# draft1.net
KiCad netlist of a schematic drawn in EAGLE
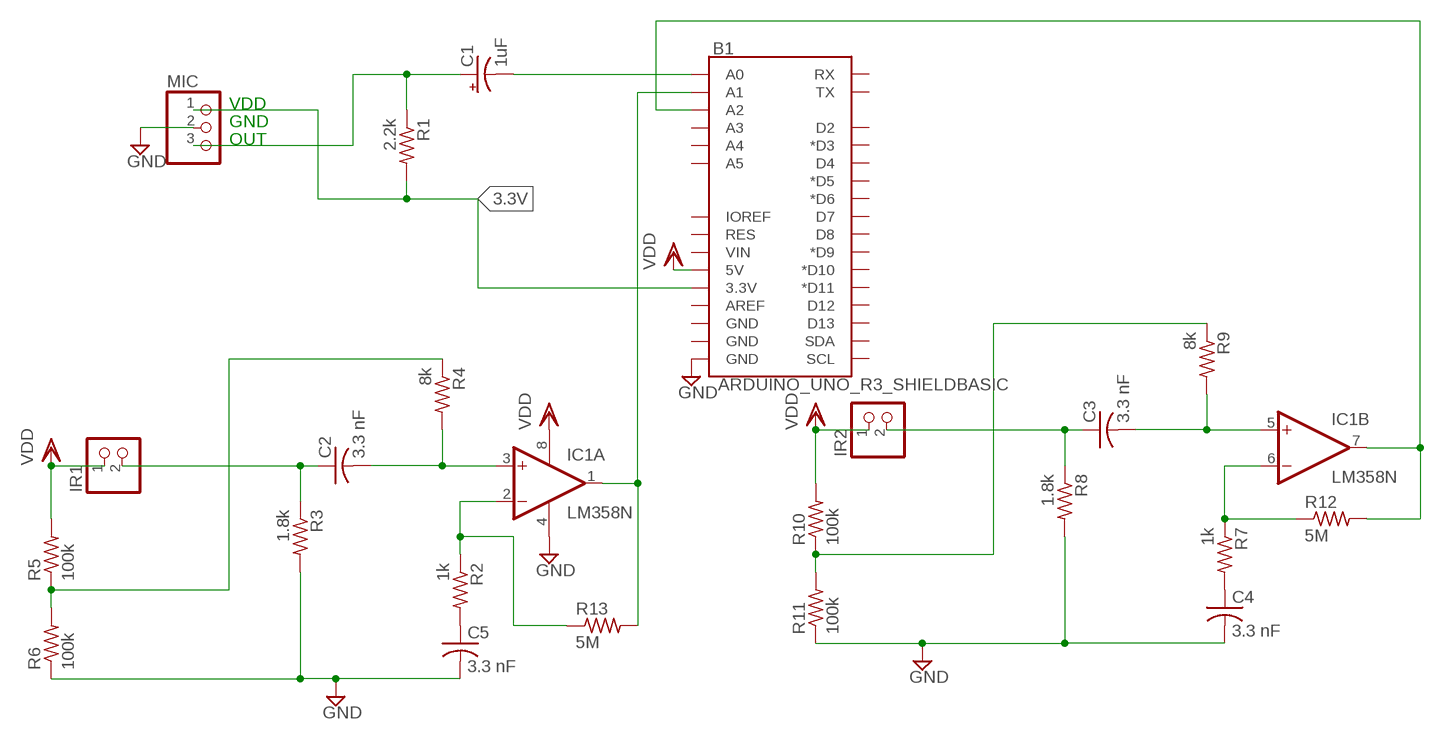
[diagram p0: schematic, sheet 1]

(export (version "E")
  (design (tool "Eeschema 10.0.6"))
  (components
    (comp (ref "B1")
      (value "ARDUINO_UNO_R3_SHIELDBASIC")
      (footprint "eagle-import:UNO_R3_SHIELD")
      (libsource (lib "eagle-import") (part "ARDUINO_UNO_R3_SHIELDBASIC"))
    )
    (comp (ref "C1")
      (value "1uF")
      (footprint "eagle-import:E5-6")
      (libsource (lib "eagle-import") (part "CPOL-USE5-6"))
    )
    (comp (ref "C2")
      (value "3.3 nF")
      (footprint "eagle-import:C025-040X050")
      (libsource (lib "eagle-import") (part "C-US025-040X050"))
    )
    (comp (ref "C3")
      (value "3.3 nF")
      (footprint "eagle-import:C025-040X050")
      (libsource (lib "eagle-import") (part "C-US025-040X050"))
    )
    (comp (ref "C4")
      (value "3.3 nF")
      (footprint "eagle-import:C025-040X050")
      (libsource (lib "eagle-import") (part "C-US025-040X050"))
    )
    (comp (ref "C5")
      (value "3.3 nF")
      (footprint "eagle-import:C025-040X050")
      (libsource (lib "eagle-import") (part "C-US025-040X050"))
    )
    (comp (ref "IC1")
      (value "LM358N")
      (footprint "eagle-import:DIL08")
      (libsource (lib "eagle-import") (part "LM358N"))
    )
    (comp (ref "IR1")
      (value "PINHD-1X2")
      (footprint "eagle-import:1X02")
      (libsource (lib "eagle-import") (part "PINHD-1X2"))
    )
    (comp (ref "IR2")
      (value "PINHD-1X2")
      (footprint "eagle-import:1X02")
      (libsource (lib "eagle-import") (part "PINHD-1X2"))
    )
    (comp (ref "MIC")
      (value "PINHD-1X3")
      (footprint "eagle-import:1X03")
      (libsource (lib "eagle-import") (part "PINHD-1X3"))
    )
    (comp (ref "R1")
      (value "2.2k")
      (footprint "eagle-import:0207_7")
      (libsource (lib "eagle-import") (part "rcl_334_R-US_0207/7"))
    )
    (comp (ref "R2")
      (value "1k")
      (footprint "eagle-import:0207_7")
      (libsource (lib "eagle-import") (part "rcl_334_R-US_0207/7"))
    )
    (comp (ref "R3")
      (value "1.8k")
      (footprint "eagle-import:0207_7")
      (libsource (lib "eagle-import") (part "rcl_334_R-US_0207/7"))
    )
    (comp (ref "R4")
      (value "8k")
      (footprint "eagle-import:0207_7")
      (libsource (lib "eagle-import") (part "rcl_334_R-US_0207/7"))
    )
    (comp (ref "R5")
      (value "100k")
      (footprint "eagle-import:0207_7")
      (libsource (lib "eagle-import") (part "R-US_0207/7"))
    )
    (comp (ref "R6")
      (value "100k")
      (footprint "eagle-import:0207_7")
      (libsource (lib "eagle-import") (part "R-US_0207/7"))
    )
    (comp (ref "R7")
      (value "1k")
      (footprint "eagle-import:0207_7")
      (libsource (lib "eagle-import") (part "rcl_334_R-US_0207/7"))
    )
    (comp (ref "R8")
      (value "1.8k")
      (footprint "eagle-import:0207_7")
      (libsource (lib "eagle-import") (part "rcl_334_R-US_0207/7"))
    )
    (comp (ref "R9")
      (value "8k")
      (footprint "eagle-import:0207_7")
      (libsource (lib "eagle-import") (part "rcl_334_R-US_0207/7"))
    )
    (comp (ref "R10")
      (value "100k")
      (footprint "eagle-import:0207_7")
      (libsource (lib "eagle-import") (part "R-US_0207/7"))
    )
    (comp (ref "R11")
      (value "100k")
      (footprint "eagle-import:0207_7")
      (libsource (lib "eagle-import") (part "R-US_0207/7"))
    )
    (comp (ref "R12")
      (value "5M")
      (footprint "eagle-import:0207_7")
      (libsource (lib "eagle-import") (part "rcl_334_R-US_0207/7"))
    )
    (comp (ref "R13")
      (value "5M")
      (footprint "eagle-import:0207_7")
      (libsource (lib "eagle-import") (part "rcl_334_R-US_0207/7"))
    )
  )
  (nets
    (net (code "1") (name "3.3V") (class "Default")
      (node (ref "B1") (pin "3.3V") (pinfunction "3.3V_3.3V") (pintype "bidirectional"))
      (node (ref "MIC") (pin "1") (pinfunction "1_1") (pintype "passive"))
      (node (ref "R1") (pin "2") (pinfunction "2_2") (pintype "passive"))
    )
    (net (code "2") (name "GND") (class "Default")
      (node (ref "B1") (pin "GND@0") (pinfunction "GND_GND@0") (pintype "bidirectional"))
      (node (ref "C4") (pin "2") (pinfunction "2_2") (pintype "passive"))
      (node (ref "C5") (pin "2") (pinfunction "2_2") (pintype "passive"))
      (node (ref "IC1") (pin "4") (pinfunction "V-_4") (pintype "power_in"))
      (node (ref "MIC") (pin "2") (pinfunction "2_2") (pintype "passive"))
      (node (ref "R11") (pin "1") (pinfunction "1_1") (pintype "passive"))
      (node (ref "R3") (pin "2") (pinfunction "2_2") (pintype "passive"))
      (node (ref "R6") (pin "1") (pinfunction "1_1") (pintype "passive"))
      (node (ref "R8") (pin "2") (pinfunction "2_2") (pintype "passive"))
    )
    (net (code "3") (name "Net-(B1-PadA0)") (class "Default")
      (node (ref "B1") (pin "A0") (pinfunction "A0_A0") (pintype "bidirectional"))
      (node (ref "C1") (pin "-") (pinfunction "-_-") (pintype "passive"))
    )
    (net (code "4") (name "Net-(C1-Pad+)") (class "Default")
      (node (ref "C1") (pin "+") (pinfunction "+_+") (pintype "passive"))
      (node (ref "MIC") (pin "3") (pinfunction "3_3") (pintype "passive"))
      (node (ref "R1") (pin "1") (pinfunction "1_1") (pintype "passive"))
    )
    (net (code "5") (name "Net-(C2-Pad1)") (class "Default")
      (node (ref "C2") (pin "1") (pinfunction "1_1") (pintype "passive"))
      (node (ref "IR1") (pin "2") (pinfunction "2_2") (pintype "passive"))
      (node (ref "R3") (pin "1") (pinfunction "1_1") (pintype "passive"))
    )
    (net (code "6") (name "Net-(C3-Pad1)") (class "Default")
      (node (ref "C3") (pin "1") (pinfunction "1_1") (pintype "passive"))
      (node (ref "IR2") (pin "2") (pinfunction "2_2") (pintype "passive"))
      (node (ref "R8") (pin "1") (pinfunction "1_1") (pintype "passive"))
    )
    (net (code "7") (name "Net-(C4-Pad1)") (class "Default")
      (node (ref "C4") (pin "1") (pinfunction "1_1") (pintype "passive"))
      (node (ref "R7") (pin "2") (pinfunction "2_2") (pintype "passive"))
    )
    (net (code "8") (name "Net-(C5-Pad1)") (class "Default")
      (node (ref "C5") (pin "1") (pinfunction "1_1") (pintype "passive"))
      (node (ref "R2") (pin "2") (pinfunction "2_2") (pintype "passive"))
    )
    (net (code "9") (name "Net-(IC1A-+IN)") (class "Default")
      (node (ref "C2") (pin "2") (pinfunction "2_2") (pintype "passive"))
      (node (ref "IC1") (pin "3") (pinfunction "+IN_3") (pintype "input"))
      (node (ref "R4") (pin "2") (pinfunction "2_2") (pintype "passive"))
    )
    (net (code "10") (name "Net-(IC1A--IN)") (class "Default")
      (node (ref "IC1") (pin "2") (pinfunction "-IN_2") (pintype "input"))
      (node (ref "R13") (pin "1") (pinfunction "1_1") (pintype "passive"))
      (node (ref "R2") (pin "1") (pinfunction "1_1") (pintype "passive"))
    )
    (net (code "11") (name "Net-(IC1A-OUT)") (class "Default")
      (node (ref "B1") (pin "A1") (pinfunction "A1_A1") (pintype "bidirectional"))
      (node (ref "IC1") (pin "1") (pinfunction "OUT_1") (pintype "output"))
      (node (ref "R13") (pin "2") (pinfunction "2_2") (pintype "passive"))
    )
    (net (code "12") (name "Net-(IC1B-+IN)") (class "Default")
      (node (ref "C3") (pin "2") (pinfunction "2_2") (pintype "passive"))
      (node (ref "IC1") (pin "5") (pinfunction "+IN_5") (pintype "input"))
      (node (ref "R9") (pin "2") (pinfunction "2_2") (pintype "passive"))
    )
    (net (code "13") (name "Net-(IC1B--IN)") (class "Default")
      (node (ref "IC1") (pin "6") (pinfunction "-IN_6") (pintype "input"))
      (node (ref "R12") (pin "1") (pinfunction "1_1") (pintype "passive"))
      (node (ref "R7") (pin "1") (pinfunction "1_1") (pintype "passive"))
    )
    (net (code "14") (name "Net-(IC1B-OUT)") (class "Default")
      (node (ref "B1") (pin "A2") (pinfunction "A2_A2") (pintype "bidirectional"))
      (node (ref "IC1") (pin "7") (pinfunction "OUT_7") (pintype "output"))
      (node (ref "R12") (pin "2") (pinfunction "2_2") (pintype "passive"))
    )
    (net (code "15") (name "Net-(R4-Pad1)") (class "Default")
      (node (ref "R4") (pin "1") (pinfunction "1_1") (pintype "passive"))
      (node (ref "R5") (pin "1") (pinfunction "1_1") (pintype "passive"))
      (node (ref "R6") (pin "2") (pinfunction "2_2") (pintype "passive"))
    )
    (net (code "16") (name "Net-(R10-Pad1)") (class "Default")
      (node (ref "R10") (pin "1") (pinfunction "1_1") (pintype "passive"))
      (node (ref "R11") (pin "2") (pinfunction "2_2") (pintype "passive"))
      (node (ref "R9") (pin "1") (pinfunction "1_1") (pintype "passive"))
    )
    (net (code "17") (name "VDD") (class "Default")
      (node (ref "B1") (pin "5V") (pinfunction "5V_5V") (pintype "bidirectional"))
      (node (ref "IC1") (pin "8") (pinfunction "V+_8") (pintype "power_in"))
      (node (ref "IR1") (pin "1") (pinfunction "1_1") (pintype "passive"))
      (node (ref "IR2") (pin "1") (pinfunction "1_1") (pintype "passive"))
      (node (ref "R10") (pin "2") (pinfunction "2_2") (pintype "passive"))
      (node (ref "R5") (pin "2") (pinfunction "2_2") (pintype "passive"))
    )
    (net (code "18") (name "unconnected-(B1-*D3-PadD3)") (class "Default")
      (node (ref "B1") (pin "D3") (pinfunction "*D3_D3") (pintype "bidirectional"))
    )
    (net (code "19") (name "unconnected-(B1-*D5-PadD5)") (class "Default")
      (node (ref "B1") (pin "D5") (pinfunction "*D5_D5") (pintype "bidirectional"))
    )
    (net (code "20") (name "unconnected-(B1-*D6-PadD6)") (class "Default")
      (node (ref "B1") (pin "D6") (pinfunction "*D6_D6") (pintype "bidirectional"))
    )
    (net (code "21") (name "unconnected-(B1-*D9-PadD9)") (class "Default")
      (node (ref "B1") (pin "D9") (pinfunction "*D9_D9") (pintype "bidirectional"))
    )
    (net (code "22") (name "unconnected-(B1-*D10-PadD10)") (class "Default")
      (node (ref "B1") (pin "D10") (pinfunction "*D10_D10") (pintype "bidirectional"))
    )
    (net (code "23") (name "unconnected-(B1-*D11-PadD11)") (class "Default")
      (node (ref "B1") (pin "D11") (pinfunction "*D11_D11") (pintype "bidirectional"))
    )
    (net (code "24") (name "unconnected-(B1-GND-PadGND@1)") (class "Default")
      (node (ref "B1") (pin "GND@1") (pinfunction "GND_GND@1") (pintype "bidirectional"))
    )
    (net (code "25") (name "unconnected-(B1-GND-PadGND@2)") (class "Default")
      (node (ref "B1") (pin "GND@2") (pinfunction "GND_GND@2") (pintype "bidirectional"))
    )
    (net (code "26") (name "unconnected-(B1-PadA3)") (class "Default")
      (node (ref "B1") (pin "A3") (pinfunction "A3_A3") (pintype "bidirectional"))
    )
    (net (code "27") (name "unconnected-(B1-PadA4)") (class "Default")
      (node (ref "B1") (pin "A4") (pinfunction "A4_A4") (pintype "bidirectional"))
    )
    (net (code "28") (name "unconnected-(B1-PadA5)") (class "Default")
      (node (ref "B1") (pin "A5") (pinfunction "A5_A5") (pintype "bidirectional"))
    )
    (net (code "29") (name "unconnected-(B1-PadAREF)") (class "Default")
      (node (ref "B1") (pin "AREF") (pinfunction "AREF_AREF") (pintype "bidirectional"))
    )
    (net (code "30") (name "unconnected-(B1-PadD2)") (class "Default")
      (node (ref "B1") (pin "D2") (pinfunction "D2_D2") (pintype "bidirectional"))
    )
    (net (code "31") (name "unconnected-(B1-PadD4)") (class "Default")
      (node (ref "B1") (pin "D4") (pinfunction "D4_D4") (pintype "bidirectional"))
    )
    (net (code "32") (name "unconnected-(B1-PadD7)") (class "Default")
      (node (ref "B1") (pin "D7") (pinfunction "D7_D7") (pintype "bidirectional"))
    )
    (net (code "33") (name "unconnected-(B1-PadD8)") (class "Default")
      (node (ref "B1") (pin "D8") (pinfunction "D8_D8") (pintype "bidirectional"))
    )
    (net (code "34") (name "unconnected-(B1-PadD12)") (class "Default")
      (node (ref "B1") (pin "D12") (pinfunction "D12_D12") (pintype "bidirectional"))
    )
    (net (code "35") (name "unconnected-(B1-PadD13)") (class "Default")
      (node (ref "B1") (pin "D13") (pinfunction "D13_D13") (pintype "bidirectional"))
    )
    (net (code "36") (name "unconnected-(B1-PadIOREF)") (class "Default")
      (node (ref "B1") (pin "IOREF") (pinfunction "IOREF_IOREF") (pintype "bidirectional"))
    )
    (net (code "37") (name "unconnected-(B1-PadRES)") (class "Default")
      (node (ref "B1") (pin "RES") (pinfunction "RES_RES") (pintype "bidirectional"))
    )
    (net (code "38") (name "unconnected-(B1-PadRX)") (class "Default")
      (node (ref "B1") (pin "RX") (pinfunction "RX_RX") (pintype "bidirectional"))
    )
    (net (code "39") (name "unconnected-(B1-PadSCL)") (class "Default")
      (node (ref "B1") (pin "SCL") (pinfunction "SCL_SCL") (pintype "bidirectional"))
    )
    (net (code "40") (name "unconnected-(B1-PadSDA)") (class "Default")
      (node (ref "B1") (pin "SDA") (pinfunction "SDA_SDA") (pintype "bidirectional"))
    )
    (net (code "41") (name "unconnected-(B1-PadTX)") (class "Default")
      (node (ref "B1") (pin "TX") (pinfunction "TX_TX") (pintype "bidirectional"))
    )
    (net (code "42") (name "unconnected-(B1-PadVIN)") (class "Default")
      (node (ref "B1") (pin "VIN") (pinfunction "VIN_VIN") (pintype "bidirectional"))
    )
  )
)
